# version_1_1.net
KiCad netlist of a schematic drawn in EAGLE
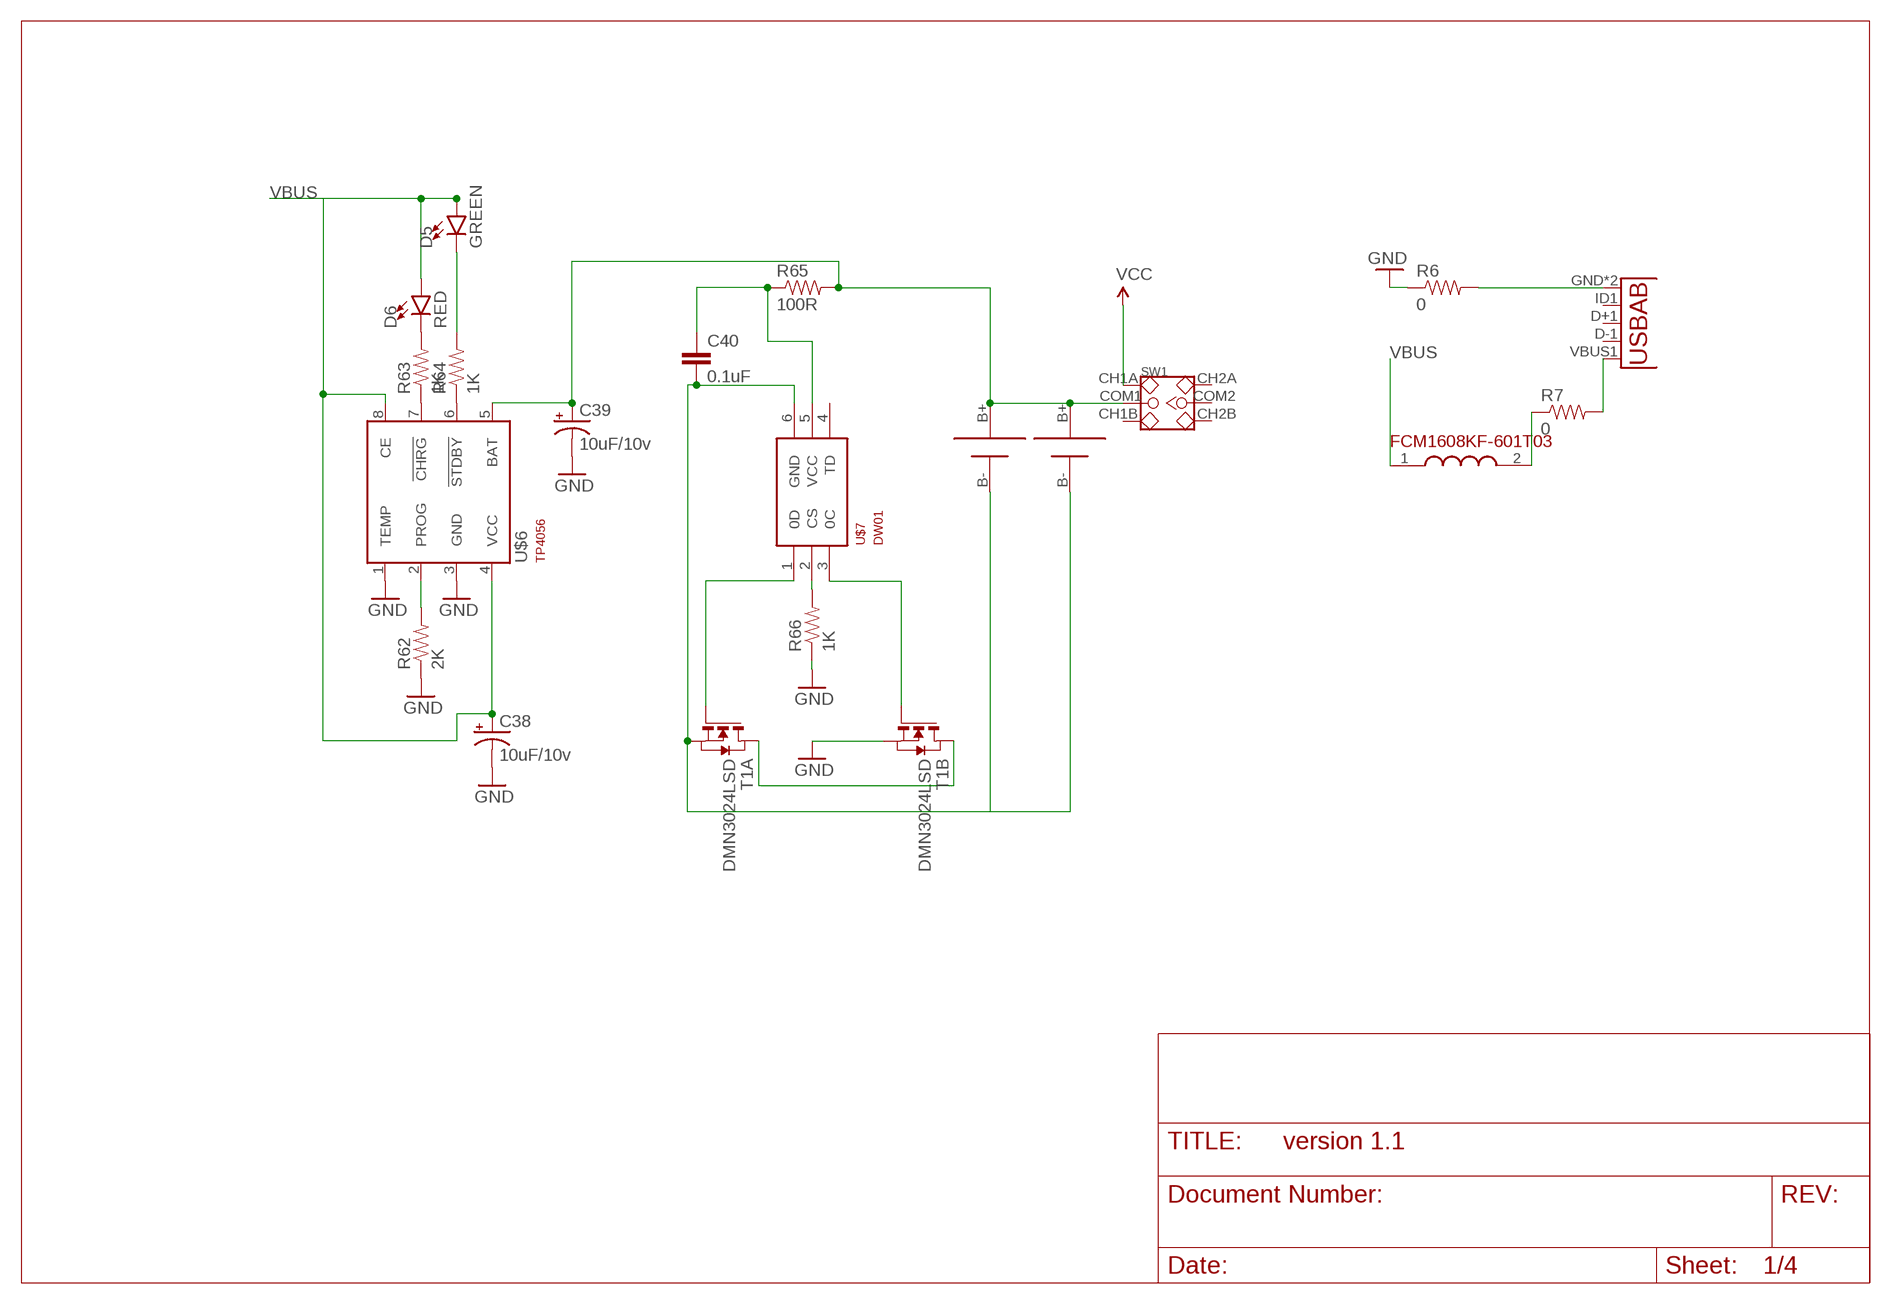
[diagram p0: schematic, sheet 1]
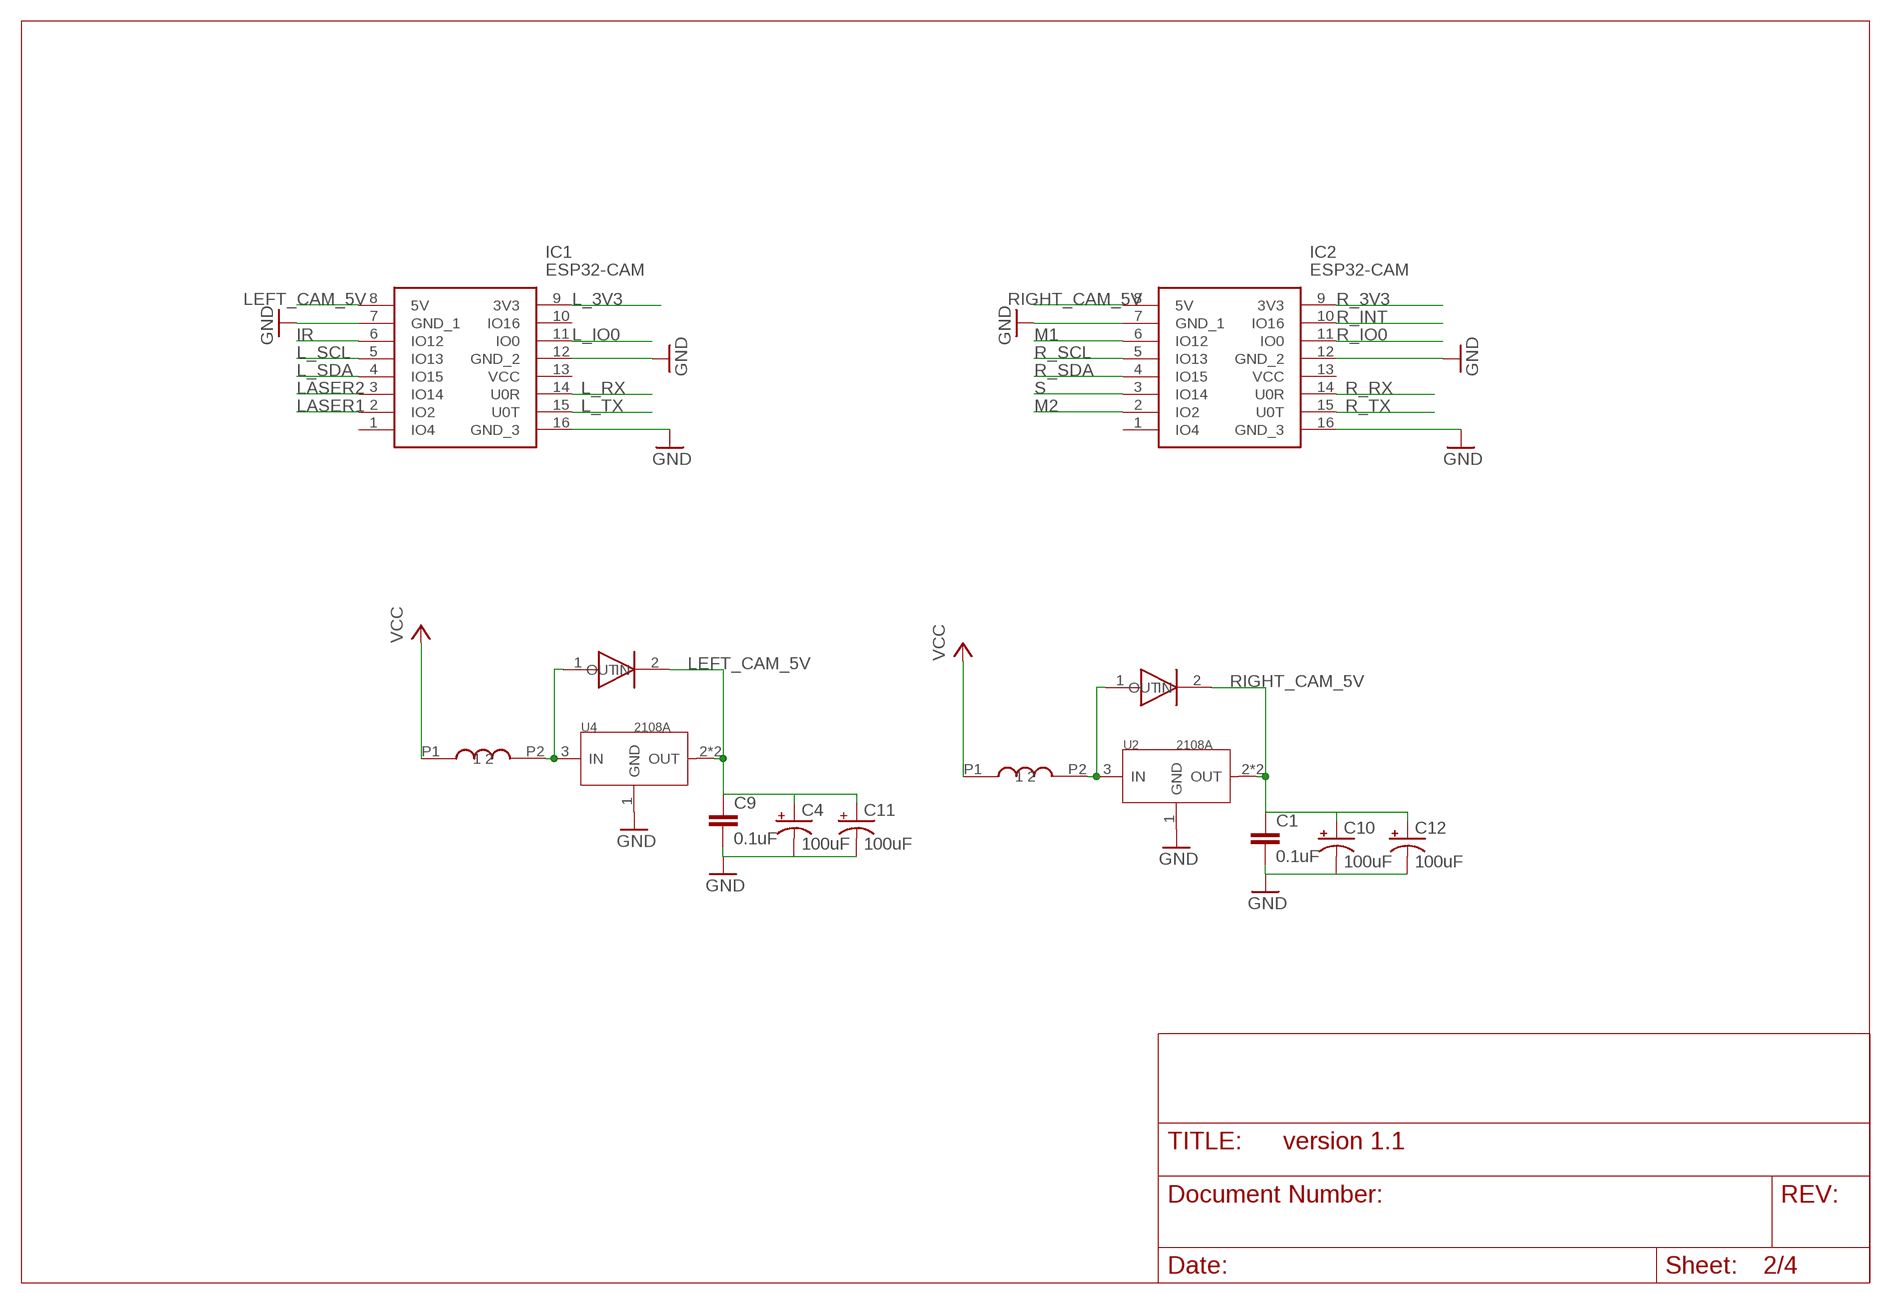
[diagram p1: schematic, sheet 2]
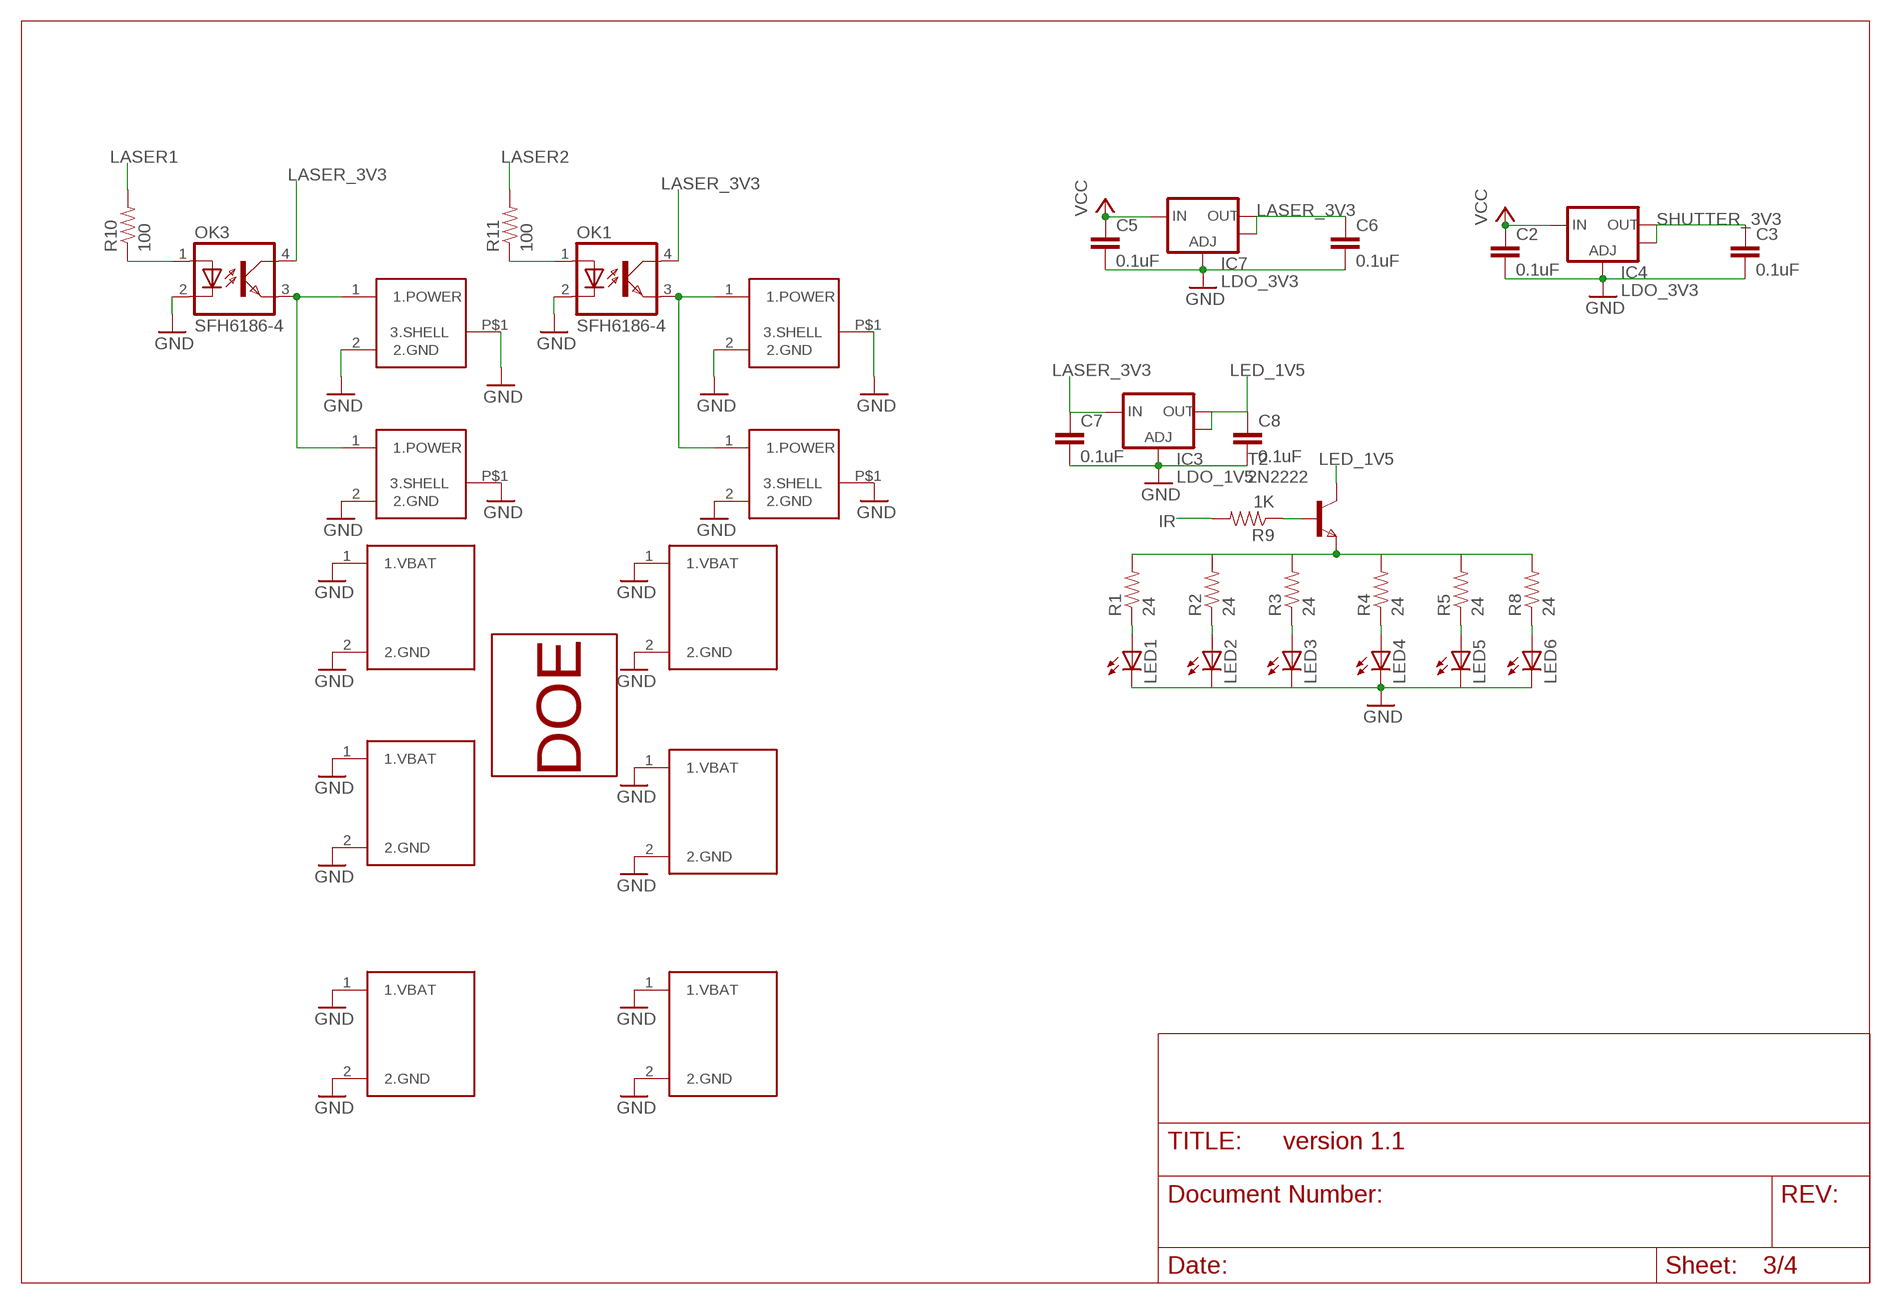
[diagram p2: schematic, sheet 3]
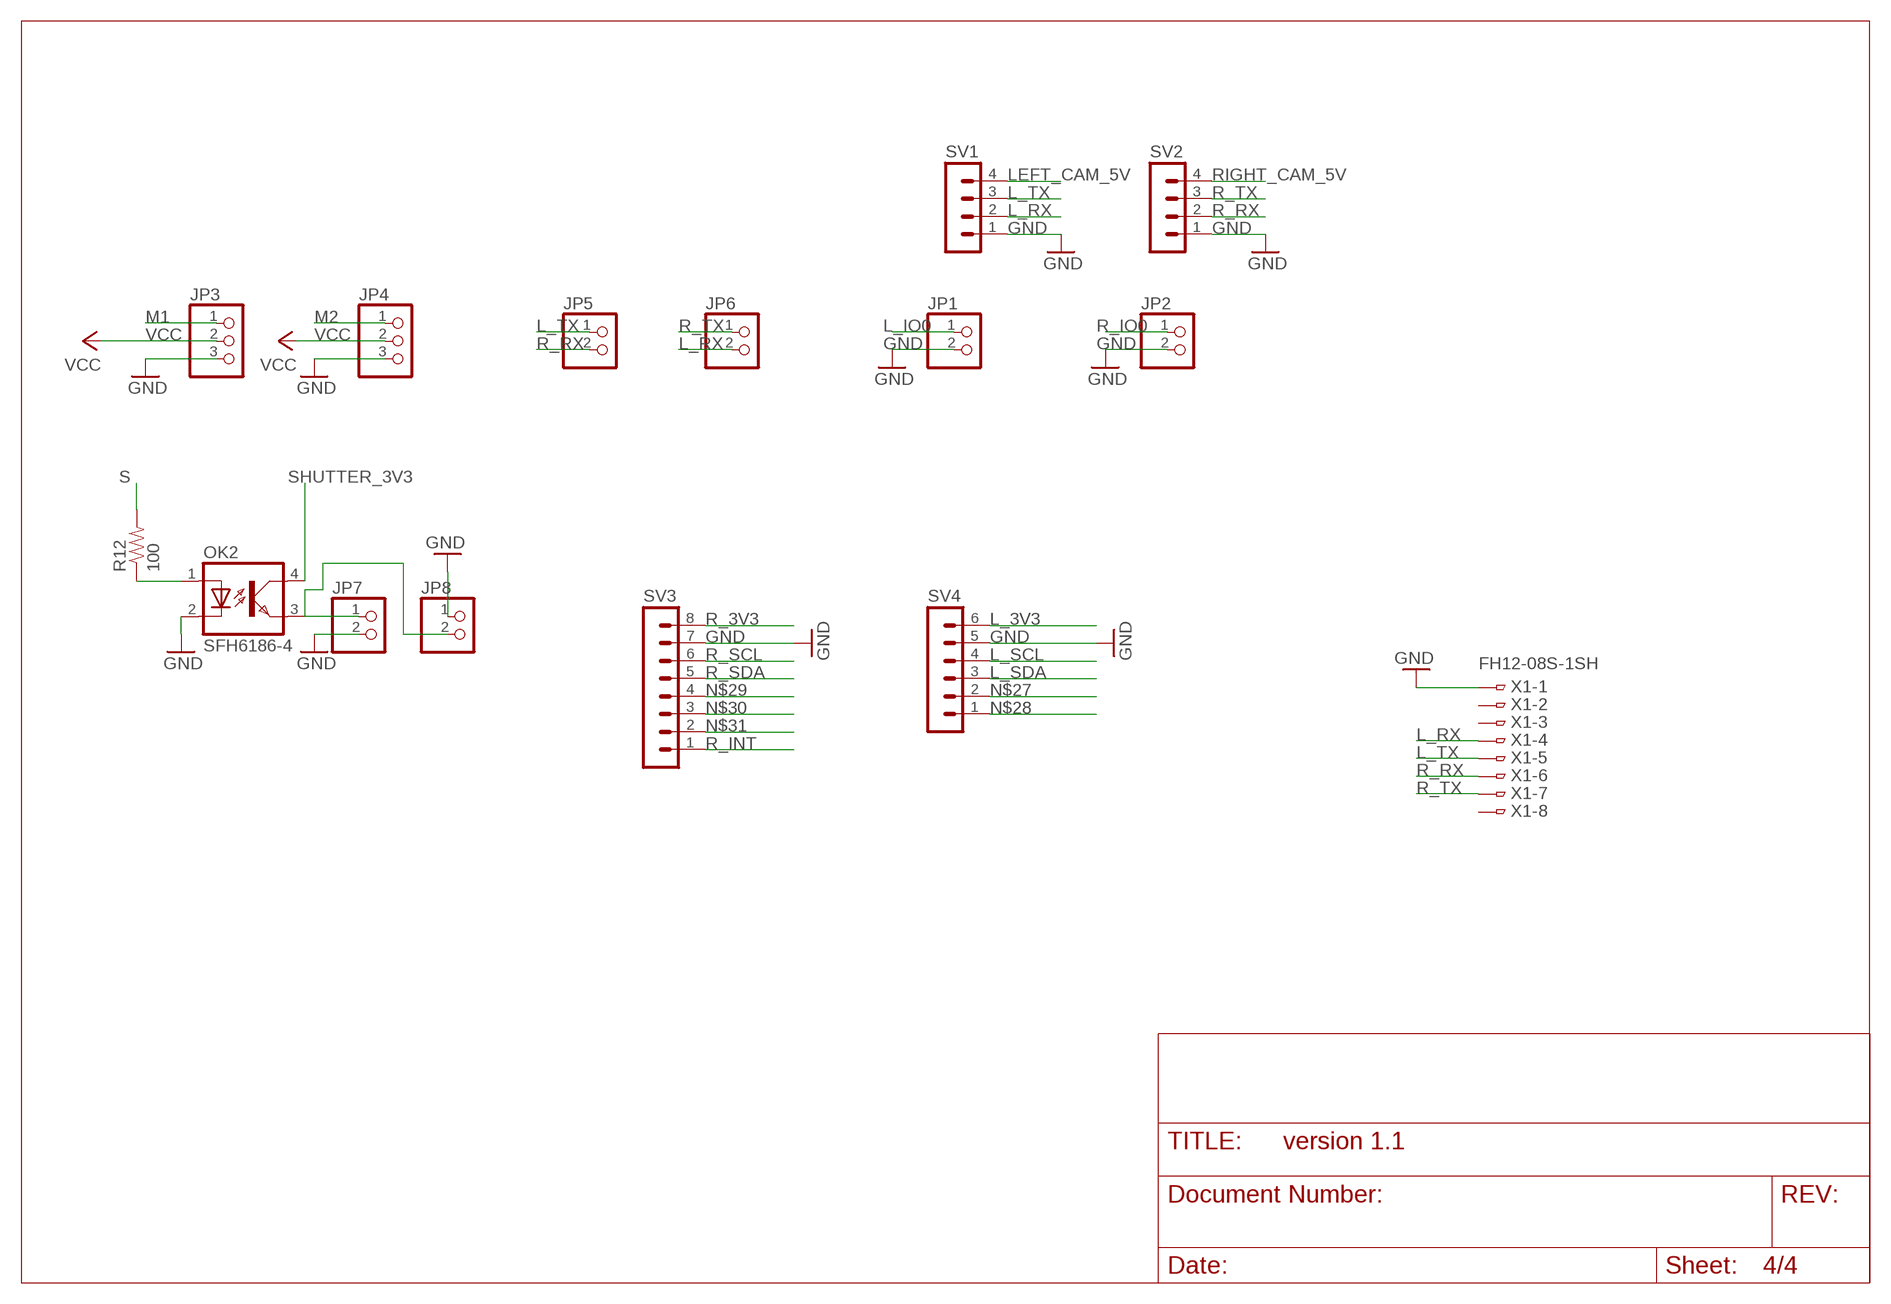
[diagram p3: schematic, sheet 4]

(export (version "E")
  (design (tool "Eeschema 10.0.6"))
  (components
    (comp (ref "C2")
      (value "0.1uF")
      (footprint "eagle-import:0603-CAP")
      (libsource (lib "eagle-import") (part "0.1UF-100V-10%(0603)"))
    )
    (comp (ref "C3")
      (value "0.1uF")
      (footprint "eagle-import:0603-CAP")
      (libsource (lib "eagle-import") (part "0.1UF-100V-10%(0603)"))
    )
    (comp (ref "C5")
      (value "0.1uF")
      (footprint "eagle-import:0603-CAP")
      (libsource (lib "eagle-import") (part "0.1UF-100V-10%(0603)"))
    )
    (comp (ref "C6")
      (value "0.1uF")
      (footprint "eagle-import:0603-CAP")
      (libsource (lib "eagle-import") (part "0.1UF-100V-10%(0603)"))
    )
    (comp (ref "C7")
      (value "0.1uF")
      (footprint "eagle-import:0603-CAP")
      (libsource (lib "eagle-import") (part "0.1UF-100V-10%(0603)"))
    )
    (comp (ref "C8")
      (value "0.1uF")
      (footprint "eagle-import:0603-CAP")
      (libsource (lib "eagle-import") (part "0.1UF-100V-10%(0603)"))
    )
    (comp (ref "IC3")
      (value "LDO_1V5")
      (footprint "eagle-import:SOT223")
      (libsource (lib "eagle-import") (part "V_REG_LM1117SOT223"))
    )
    (comp (ref "IC4")
      (value "LDO_3V3")
      (footprint "eagle-import:SOT223")
      (libsource (lib "eagle-import") (part "V_REG_LM1117SOT223"))
    )
    (comp (ref "IC7")
      (value "LDO_3V3")
      (footprint "eagle-import:SOT223")
      (libsource (lib "eagle-import") (part "V_REG_LM1117SOT223"))
    )
    (comp (ref "LED1")
      (value "LED5MM")
      (footprint "eagle-import:LED5MM")
      (libsource (lib "eagle-import") (part "LED5MM"))
    )
    (comp (ref "LED2")
      (value "LED5MM")
      (footprint "eagle-import:LED5MM")
      (libsource (lib "eagle-import") (part "LED5MM"))
    )
    (comp (ref "LED3")
      (value "LED5MM")
      (footprint "eagle-import:LED5MM")
      (libsource (lib "eagle-import") (part "LED5MM"))
    )
    (comp (ref "LED4")
      (value "LED5MM")
      (footprint "eagle-import:LED5MM")
      (libsource (lib "eagle-import") (part "LED5MM"))
    )
    (comp (ref "LED5")
      (value "LED5MM")
      (footprint "eagle-import:LED5MM")
      (libsource (lib "eagle-import") (part "LED5MM"))
    )
    (comp (ref "LED6")
      (value "LED5MM")
      (footprint "eagle-import:LED5MM")
      (libsource (lib "eagle-import") (part "LED5MM"))
    )
    (comp (ref "OK1")
      (value "SFH6186-4")
      (footprint "eagle-import:SMD4-7")
      (fields (field (name "MF") "VISHAY/TELEFUNKEN"))
      (libsource (lib "eagle-import") (part "SFH618?6-4"))
    )
    (comp (ref "OK3")
      (value "SFH6186-4")
      (footprint "eagle-import:SMD4-7")
      (fields (field (name "MF") "VISHAY/TELEFUNKEN"))
      (libsource (lib "eagle-import") (part "SFH618?6-4"))
    )
    (comp (ref "R1")
      (value "24")
      (footprint "eagle-import:0603-RES")
      (libsource (lib "eagle-import") (part "1KOHM1/10W1%(0603)"))
    )
    (comp (ref "R2")
      (value "24")
      (footprint "eagle-import:0603-RES")
      (libsource (lib "eagle-import") (part "1KOHM1/10W1%(0603)"))
    )
    (comp (ref "R3")
      (value "24")
      (footprint "eagle-import:0603-RES")
      (libsource (lib "eagle-import") (part "1KOHM1/10W1%(0603)"))
    )
    (comp (ref "R4")
      (value "24")
      (footprint "eagle-import:0603-RES")
      (libsource (lib "eagle-import") (part "1KOHM1/10W1%(0603)"))
    )
    (comp (ref "R5")
      (value "24")
      (footprint "eagle-import:0603-RES")
      (libsource (lib "eagle-import") (part "1KOHM1/10W1%(0603)"))
    )
    (comp (ref "R8")
      (value "24")
      (footprint "eagle-import:0603-RES")
      (libsource (lib "eagle-import") (part "1KOHM1/10W1%(0603)"))
    )
    (comp (ref "R9")
      (value "1K")
      (footprint "eagle-import:0603-RES")
      (libsource (lib "eagle-import") (part "1KOHM1/10W1%(0603)"))
    )
    (comp (ref "R10")
      (value "100")
      (footprint "eagle-import:0603-RES")
      (libsource (lib "eagle-import") (part "1KOHM1/10W1%(0603)"))
    )
    (comp (ref "R11")
      (value "100")
      (footprint "eagle-import:0603-RES")
      (libsource (lib "eagle-import") (part "1KOHM1/10W1%(0603)"))
    )
    (comp (ref "T2")
      (value "2N2222")
      (footprint "eagle-import:SOT-23")
      (libsource (lib "eagle-import") (part "FMMT451"))
    )
    (comp (ref "U$1")
      (value "OD-6.5MM-LASER")
      (footprint "eagle-import:OD-6.5MM-LASER")
      (libsource (lib "eagle-import") (part "OD-6.5MM-LASER"))
    )
    (comp (ref "U$2")
      (value "OD-6.5MM-LASER")
      (footprint "eagle-import:OD-6.5MM-LASER")
      (libsource (lib "eagle-import") (part "OD-6.5MM-LASER"))
    )
    (comp (ref "U$3")
      (value "DOE-MODULE")
      (footprint "eagle-import:DOE-MODULE")
      (libsource (lib "eagle-import") (part "DOE-MODULE"))
    )
    (comp (ref "U$9")
      (value "CR2025-HOLDER")
      (footprint "eagle-import:CR2025-HOLDER")
      (libsource (lib "eagle-import") (part "CR2025-HOLDER"))
    )
    (comp (ref "U$10")
      (value "CR2025-HOLDER")
      (footprint "eagle-import:CR2025-HOLDER")
      (libsource (lib "eagle-import") (part "CR2025-HOLDER"))
    )
    (comp (ref "U$11")
      (value "CR2025-HOLDER")
      (footprint "eagle-import:CR2025-HOLDER")
      (libsource (lib "eagle-import") (part "CR2025-HOLDER"))
    )
    (comp (ref "U$12")
      (value "CR2025-HOLDER")
      (footprint "eagle-import:CR2025-HOLDER")
      (libsource (lib "eagle-import") (part "CR2025-HOLDER"))
    )
    (comp (ref "U$17")
      (value "CR2025-HOLDER")
      (footprint "eagle-import:CR2025-HOLDER")
      (libsource (lib "eagle-import") (part "CR2025-HOLDER"))
    )
    (comp (ref "U$18")
      (value "CR2025-HOLDER")
      (footprint "eagle-import:CR2025-HOLDER")
      (libsource (lib "eagle-import") (part "CR2025-HOLDER"))
    )
    (comp (ref "U$19")
      (value "OD-9MM-LASER")
      (footprint "eagle-import:OD-9MM-LASER")
      (libsource (lib "eagle-import") (part "OD-9MM-LASER"))
    )
    (comp (ref "U$20")
      (value "OD-12MM-LASER")
      (footprint "eagle-import:OD-12MM-LASER")
      (libsource (lib "eagle-import") (part "OD-12MM-LASER"))
    )
    (comp (ref "C38")
      (value "10uF/10v")
      (footprint "eagle-import:EIA3216-KIT")
      (libsource (lib "eagle-import") (part "CAP_POL1206-KIT"))
    )
    (comp (ref "C39")
      (value "10uF/10v")
      (footprint "eagle-import:EIA3216-KIT")
      (libsource (lib "eagle-import") (part "CAP_POL1206-KIT"))
    )
    (comp (ref "C40")
      (value "0.1uF")
      (footprint "eagle-import:0603-CAP")
      (libsource (lib "eagle-import") (part "0.1UF-100V-10%(0603)"))
    )
    (comp (ref "D5")
      (value "GREEN")
      (footprint "eagle-import:LED-0603")
      (libsource (lib "eagle-import") (part "LED-BLUE0603"))
    )
    (comp (ref "D6")
      (value "RED")
      (footprint "eagle-import:LED-0603")
      (libsource (lib "eagle-import") (part "LED-BLUE0603"))
    )
    (comp (ref "R6")
      (value "0")
      (footprint "eagle-import:0805")
      (libsource (lib "eagle-import") (part "RESISTOR0805-RES"))
    )
    (comp (ref "R7")
      (value "0")
      (footprint "eagle-import:0805")
      (libsource (lib "eagle-import") (part "RESISTOR0805-RES"))
    )
    (comp (ref "R62")
      (value "2K")
      (footprint "eagle-import:0603-RES")
      (libsource (lib "eagle-import") (part "1KOHM1/10W1%(0603)"))
    )
    (comp (ref "R63")
      (value "1K")
      (footprint "eagle-import:0603-RES")
      (libsource (lib "eagle-import") (part "1KOHM1/10W1%(0603)"))
    )
    (comp (ref "R64")
      (value "1K")
      (footprint "eagle-import:0603-RES")
      (libsource (lib "eagle-import") (part "1KOHM1/10W1%(0603)"))
    )
    (comp (ref "R65")
      (value "100R")
      (footprint "eagle-import:0603-RES")
      (libsource (lib "eagle-import") (part "1KOHM1/10W1%(0603)"))
    )
    (comp (ref "R66")
      (value "1K")
      (footprint "eagle-import:0603-RES")
      (libsource (lib "eagle-import") (part "1KOHM1/10W1%(0603)"))
    )
    (comp (ref "SW1")
      (value "SMD-TOGGLE-SWITCH-2CH(2X3P-7X3.5MM)")
      (footprint "eagle-import:SW6-2.54-SMD-7.0X3.5X1.5MM")
      (libsource (lib "eagle-import") (part "SMD-TOGGLE-SWITCH-2CH(2X3P-7X3.5MM)"))
    )
    (comp (ref "T1")
      (value "DMN3024LSD")
      (footprint "eagle-import:TSSOP-8")
      (libsource (lib "eagle-import") (part "DMN3024LSD"))
    )
    (comp (ref "U$4")
      (value "FCM1608KF-601T03")
      (footprint "eagle-import:FCM1608KF-601T03")
      (libsource (lib "eagle-import") (part "FCM1608KF-601T03"))
    )
    (comp (ref "U$5")
      (value "18650SMD")
      (footprint "eagle-import:18650SMD")
      (libsource (lib "eagle-import") (part "18650SMD"))
    )
    (comp (ref "U$6")
      (value "TP4056")
      (footprint "eagle-import:SOT23-8")
      (libsource (lib "eagle-import") (part "TP4056"))
    )
    (comp (ref "U$7")
      (value "DW01")
      (footprint "eagle-import:SOT23-6")
      (libsource (lib "eagle-import") (part "DW01"))
    )
    (comp (ref "U$8")
      (value "18650SMD")
      (footprint "eagle-import:18650SMD")
      (libsource (lib "eagle-import") (part "18650SMD"))
    )
    (comp (ref "U1")
      (value "USB\"\"")
      (footprint "eagle-import:USB-MICRO-SMD")
      (libsource (lib "eagle-import") (part "USB{dblquote}{dblquote}"))
    )
    (comp (ref "JP1")
      (value "PINHD-1X2")
      (footprint "eagle-import:1X02")
      (libsource (lib "eagle-import") (part "PINHD-1X2"))
    )
    (comp (ref "JP2")
      (value "PINHD-1X2")
      (footprint "eagle-import:1X02")
      (libsource (lib "eagle-import") (part "PINHD-1X2"))
    )
    (comp (ref "JP3")
      (value "PINHD-1X3")
      (footprint "eagle-import:1X03")
      (libsource (lib "eagle-import") (part "PINHD-1X3"))
    )
    (comp (ref "JP4")
      (value "PINHD-1X3")
      (footprint "eagle-import:1X03")
      (libsource (lib "eagle-import") (part "PINHD-1X3"))
    )
    (comp (ref "JP5")
      (value "PINHD-1X2")
      (footprint "eagle-import:1X02")
      (libsource (lib "eagle-import") (part "PINHD-1X2"))
    )
    (comp (ref "JP6")
      (value "PINHD-1X2")
      (footprint "eagle-import:1X02")
      (libsource (lib "eagle-import") (part "PINHD-1X2"))
    )
    (comp (ref "JP7")
      (value "PINHD-1X2")
      (footprint "eagle-import:1X02")
      (libsource (lib "eagle-import") (part "PINHD-1X2"))
    )
    (comp (ref "JP8")
      (value "PINHD-1X2")
      (footprint "eagle-import:1X02")
      (libsource (lib "eagle-import") (part "PINHD-1X2"))
    )
    (comp (ref "OK2")
      (value "SFH6186-4")
      (footprint "eagle-import:SMD4-7")
      (fields (field (name "MF") "VISHAY/TELEFUNKEN"))
      (libsource (lib "eagle-import") (part "SFH618?6-4"))
    )
    (comp (ref "R12")
      (value "100")
      (footprint "eagle-import:0603-RES")
      (libsource (lib "eagle-import") (part "1KOHM1/10W1%(0603)"))
    )
    (comp (ref "SV1")
      (value "MA04-1")
      (footprint "eagle-import:MA04-1")
      (libsource (lib "eagle-import") (part "MA04-1"))
    )
    (comp (ref "SV2")
      (value "MA04-1")
      (footprint "eagle-import:MA04-1")
      (libsource (lib "eagle-import") (part "MA04-1"))
    )
    (comp (ref "SV3")
      (value "MA08-1")
      (footprint "eagle-import:MA08-1")
      (libsource (lib "eagle-import") (part "MA08-1"))
    )
    (comp (ref "SV4")
      (value "MA06-1")
      (footprint "eagle-import:MA06-1")
      (libsource (lib "eagle-import") (part "MA06-1"))
    )
    (comp (ref "X1")
      (value "FH12-08S-1SH")
      (footprint "eagle-import:FH12-08S-1SH")
      (libsource (lib "eagle-import") (part "FH12-08S-1SH"))
    )
    (comp (ref "C1")
      (value "0.1uF")
      (footprint "eagle-import:0603-CAP")
      (libsource (lib "eagle-import") (part "0.1UF-25V-5%(0603)"))
    )
    (comp (ref "C4")
      (value "100uF")
      (footprint "eagle-import:E_7260-38R")
      (libsource (lib "eagle-import") (part "CPOL-USE/7260-38R"))
    )
    (comp (ref "C9")
      (value "0.1uF")
      (footprint "eagle-import:0603-CAP")
      (libsource (lib "eagle-import") (part "0.1UF-25V-5%(0603)"))
    )
    (comp (ref "C10")
      (value "100uF")
      (footprint "eagle-import:E_7260-38R")
      (libsource (lib "eagle-import") (part "CPOL-USE/7260-38R"))
    )
    (comp (ref "C11")
      (value "100uF")
      (footprint "eagle-import:E_7260-38R")
      (libsource (lib "eagle-import") (part "CPOL-USE/7260-38R"))
    )
    (comp (ref "C12")
      (value "100uF")
      (footprint "eagle-import:E_7260-38R")
      (libsource (lib "eagle-import") (part "CPOL-USE/7260-38R"))
    )
    (comp (ref "IC1")
      (value "ESP32-CAM")
      (footprint "eagle-import:ESP32CAM")
      (libsource (lib "eagle-import") (part "ESP32-CAM"))
    )
    (comp (ref "IC2")
      (value "ESP32-CAM")
      (footprint "eagle-import:ESP32CAM")
      (libsource (lib "eagle-import") (part "ESP32-CAM"))
    )
    (comp (ref "U$13")
      (value "CD54")
      (footprint "eagle-import:CD54")
      (libsource (lib "eagle-import") (part "CD54"))
    )
    (comp (ref "U$14")
      (value "SMA-SS34")
      (footprint "eagle-import:SMA-SS34")
      (libsource (lib "eagle-import") (part "SMA-SS34"))
    )
    (comp (ref "U$15")
      (value "SMA-SS34")
      (footprint "eagle-import:SMA-SS34")
      (libsource (lib "eagle-import") (part "SMA-SS34"))
    )
    (comp (ref "U$16")
      (value "CD54")
      (footprint "eagle-import:CD54")
      (libsource (lib "eagle-import") (part "CD54"))
    )
    (comp (ref "U2")
      (value "2108A")
      (footprint "eagle-import:SOT-89")
      (fields (field (name "MPN") "CJA1117B-3.3"))
      (libsource (lib "eagle-import") (part "PMIC-CJA1117B-3.3(SOT-89)"))
    )
    (comp (ref "U4")
      (value "2108A")
      (footprint "eagle-import:SOT-89")
      (fields (field (name "MPN") "CJA1117B-3.3"))
      (libsource (lib "eagle-import") (part "PMIC-CJA1117B-3.3(SOT-89)"))
    )
  )
  (nets
    (net (code "1") (name "GND") (class "Default")
      (node (ref "C1") (pin "2") (pinfunction "2_2") (pintype "passive"))
      (node (ref "C10") (pin "-") (pinfunction "-_-") (pintype "passive"))
      (node (ref "C11") (pin "-") (pinfunction "-_-") (pintype "passive"))
      (node (ref "C12") (pin "-") (pinfunction "-_-") (pintype "passive"))
      (node (ref "C2") (pin "2") (pinfunction "2_2") (pintype "passive"))
      (node (ref "C3") (pin "2") (pinfunction "2_2") (pintype "passive"))
      (node (ref "C38") (pin "C") (pinfunction "-_C") (pintype "passive"))
      (node (ref "C39") (pin "C") (pinfunction "-_C") (pintype "passive"))
      (node (ref "C4") (pin "-") (pinfunction "-_-") (pintype "passive"))
      (node (ref "C5") (pin "2") (pinfunction "2_2") (pintype "passive"))
      (node (ref "C6") (pin "2") (pinfunction "2_2") (pintype "passive"))
      (node (ref "C7") (pin "2") (pinfunction "2_2") (pintype "passive"))
      (node (ref "C8") (pin "2") (pinfunction "2_2") (pintype "passive"))
      (node (ref "C9") (pin "2") (pinfunction "2_2") (pintype "passive"))
      (node (ref "IC1") (pin "12") (pinfunction "GND_2_12") (pintype "bidirectional"))
      (node (ref "IC1") (pin "16") (pinfunction "GND_3_16") (pintype "bidirectional"))
      (node (ref "IC1") (pin "7") (pinfunction "GND_1_7") (pintype "bidirectional"))
      (node (ref "IC2") (pin "12") (pinfunction "GND_2_12") (pintype "bidirectional"))
      (node (ref "IC2") (pin "16") (pinfunction "GND_3_16") (pintype "bidirectional"))
      (node (ref "IC2") (pin "7") (pinfunction "GND_1_7") (pintype "bidirectional"))
      (node (ref "IC3") (pin "1") (pinfunction "ADJ_1") (pintype "input"))
      (node (ref "IC4") (pin "1") (pinfunction "ADJ_1") (pintype "input"))
      (node (ref "IC7") (pin "1") (pinfunction "ADJ_1") (pintype "input"))
      (node (ref "JP1") (pin "2") (pinfunction "2_2") (pintype "passive"))
      (node (ref "JP2") (pin "2") (pinfunction "2_2") (pintype "passive"))
      (node (ref "JP3") (pin "3") (pinfunction "3_3") (pintype "passive"))
      (node (ref "JP4") (pin "3") (pinfunction "3_3") (pintype "passive"))
      (node (ref "JP7") (pin "2") (pinfunction "2_2") (pintype "passive"))
      (node (ref "JP8") (pin "1") (pinfunction "1_1") (pintype "passive"))
      (node (ref "LED1") (pin "K") (pinfunction "C_K") (pintype "passive"))
      (node (ref "LED2") (pin "K") (pinfunction "C_K") (pintype "passive"))
      (node (ref "LED3") (pin "K") (pinfunction "C_K") (pintype "passive"))
      (node (ref "LED4") (pin "K") (pinfunction "C_K") (pintype "passive"))
      (node (ref "LED5") (pin "K") (pinfunction "C_K") (pintype "passive"))
      (node (ref "LED6") (pin "K") (pinfunction "C_K") (pintype "passive"))
      (node (ref "OK1") (pin "2") (pinfunction "C_2") (pintype "passive"))
      (node (ref "OK2") (pin "2") (pinfunction "C_2") (pintype "passive"))
      (node (ref "OK3") (pin "2") (pinfunction "C_2") (pintype "passive"))
      (node (ref "R6") (pin "1") (pinfunction "1_1") (pintype "passive"))
      (node (ref "R62") (pin "1") (pinfunction "1_1") (pintype "passive"))
      (node (ref "R66") (pin "1") (pinfunction "1_1") (pintype "passive"))
      (node (ref "SV1") (pin "1") (pinfunction "1_1") (pintype "passive"))
      (node (ref "SV2") (pin "1") (pinfunction "1_1") (pintype "passive"))
      (node (ref "SV3") (pin "7") (pinfunction "7_7") (pintype "passive"))
      (node (ref "SV4") (pin "5") (pinfunction "5_5") (pintype "passive"))
      (node (ref "T1") (pin "6") (pinfunction "S_6") (pintype "passive"))
      (node (ref "T1") (pin "7") (pinfunction "S_7") (pintype "passive"))
      (node (ref "U$1") (pin "2") (pinfunction "2.GND_2") (pintype "bidirectional"))
      (node (ref "U$1") (pin "P$1") (pinfunction "3.SHELL_P$1") (pintype "bidirectional"))
      (node (ref "U$10") (pin "1") (pinfunction "1.VBAT_1") (pintype "bidirectional"))
      (node (ref "U$10") (pin "2") (pinfunction "2.GND_2") (pintype "bidirectional"))
      (node (ref "U$11") (pin "1") (pinfunction "1.VBAT_1") (pintype "bidirectional"))
      (node (ref "U$11") (pin "2") (pinfunction "2.GND_2") (pintype "bidirectional"))
      (node (ref "U$12") (pin "1") (pinfunction "1.VBAT_1") (pintype "bidirectional"))
      (node (ref "U$12") (pin "2") (pinfunction "2.GND_2") (pintype "bidirectional"))
      (node (ref "U$17") (pin "1") (pinfunction "1.VBAT_1") (pintype "bidirectional"))
      (node (ref "U$17") (pin "2") (pinfunction "2.GND_2") (pintype "bidirectional"))
      (node (ref "U$18") (pin "1") (pinfunction "1.VBAT_1") (pintype "bidirectional"))
      (node (ref "U$18") (pin "2") (pinfunction "2.GND_2") (pintype "bidirectional"))
      (node (ref "U$19") (pin "2") (pinfunction "2.GND_2") (pintype "bidirectional"))
      (node (ref "U$19") (pin "P$1") (pinfunction "3.SHELL_P$1") (pintype "bidirectional"))
      (node (ref "U$2") (pin "2") (pinfunction "2.GND_2") (pintype "bidirectional"))
      (node (ref "U$2") (pin "P$1") (pinfunction "3.SHELL_P$1") (pintype "bidirectional"))
      (node (ref "U$20") (pin "2") (pinfunction "2.GND_2") (pintype "bidirectional"))
      (node (ref "U$20") (pin "P$1") (pinfunction "3.SHELL_P$1") (pintype "bidirectional"))
      (node (ref "U$6") (pin "1") (pinfunction "TEMP_1") (pintype "bidirectional"))
      (node (ref "U$6") (pin "3") (pinfunction "GND_3") (pintype "bidirectional"))
      (node (ref "U$9") (pin "1") (pinfunction "1.VBAT_1") (pintype "bidirectional"))
      (node (ref "U$9") (pin "2") (pinfunction "2.GND_2") (pintype "bidirectional"))
      (node (ref "U2") (pin "1") (pinfunction "GND_1") (pintype "bidirectional"))
      (node (ref "U4") (pin "1") (pinfunction "GND_1") (pintype "bidirectional"))
      (node (ref "X1") (pin "1") (pinfunction "1_1") (pintype "passive"))
    )
    (net (code "2") (name "IR") (class "Default")
      (node (ref "IC1") (pin "6") (pinfunction "IO12_6") (pintype "bidirectional"))
      (node (ref "R9") (pin "2") (pinfunction "2_2") (pintype "passive"))
    )
    (net (code "3") (name "LASER1") (class "Default")
      (node (ref "IC1") (pin "2") (pinfunction "IO2_2") (pintype "bidirectional"))
      (node (ref "R10") (pin "2") (pinfunction "2_2") (pintype "passive"))
    )
    (net (code "4") (name "LASER2") (class "Default")
      (node (ref "IC1") (pin "3") (pinfunction "IO14_3") (pintype "bidirectional"))
      (node (ref "R11") (pin "2") (pinfunction "2_2") (pintype "passive"))
    )
    (net (code "5") (name "LASER_3V3") (class "Default")
      (node (ref "C6") (pin "1") (pinfunction "1_1") (pintype "passive"))
      (node (ref "C7") (pin "1") (pinfunction "1_1") (pintype "passive"))
      (node (ref "IC3") (pin "3") (pinfunction "IN_3") (pintype "input"))
      (node (ref "IC7") (pin "2") (pinfunction "OUT_2") (pintype "output"))
      (node (ref "IC7") (pin "4") (pinfunction "OUT_4") (pintype "output"))
      (node (ref "OK1") (pin "4") (pinfunction "COL_4") (pintype "passive"))
      (node (ref "OK3") (pin "4") (pinfunction "COL_4") (pintype "passive"))
    )
    (net (code "6") (name "LED_1V5") (class "Default")
      (node (ref "C8") (pin "1") (pinfunction "1_1") (pintype "passive"))
      (node (ref "IC3") (pin "2") (pinfunction "OUT_2") (pintype "output"))
      (node (ref "IC3") (pin "4") (pinfunction "OUT_4") (pintype "output"))
      (node (ref "T2") (pin "1") (pinfunction "C_1") (pintype "passive"))
    )
    (net (code "7") (name "LEFT_CAM_5V") (class "Default")
      (node (ref "C11") (pin "+") (pinfunction "+_+") (pintype "passive"))
      (node (ref "C4") (pin "+") (pinfunction "+_+") (pintype "passive"))
      (node (ref "C9") (pin "1") (pinfunction "1_1") (pintype "passive"))
      (node (ref "IC1") (pin "8") (pinfunction "5V_8") (pintype "bidirectional"))
      (node (ref "SV1") (pin "4") (pinfunction "4_4") (pintype "passive"))
      (node (ref "U$14") (pin "2") (pinfunction "OUT_2") (pintype "bidirectional"))
      (node (ref "U4") (pin "2") (pinfunction "OUT_2") (pintype "bidirectional"))
      (node (ref "U4") (pin "4") (pinfunction "OUT_4") (pintype "bidirectional"))
    )
    (net (code "8") (name "L_3V3") (class "Default")
      (node (ref "IC1") (pin "9") (pinfunction "3V3_9") (pintype "bidirectional"))
      (node (ref "SV4") (pin "6") (pinfunction "6_6") (pintype "passive"))
    )
    (net (code "9") (name "L_IO0") (class "Default")
      (node (ref "IC1") (pin "11") (pinfunction "IO0_11") (pintype "bidirectional"))
      (node (ref "JP1") (pin "1") (pinfunction "1_1") (pintype "passive"))
    )
    (net (code "10") (name "L_RX") (class "Default")
      (node (ref "IC1") (pin "14") (pinfunction "U0R_14") (pintype "bidirectional"))
      (node (ref "JP6") (pin "2") (pinfunction "2_2") (pintype "passive"))
      (node (ref "SV1") (pin "2") (pinfunction "2_2") (pintype "passive"))
      (node (ref "X1") (pin "4") (pinfunction "1_4") (pintype "passive"))
    )
    (net (code "11") (name "L_SCL") (class "Default")
      (node (ref "IC1") (pin "5") (pinfunction "IO13_5") (pintype "bidirectional"))
      (node (ref "SV4") (pin "4") (pinfunction "4_4") (pintype "passive"))
    )
    (net (code "12") (name "L_SDA") (class "Default")
      (node (ref "IC1") (pin "4") (pinfunction "IO15_4") (pintype "bidirectional"))
      (node (ref "SV4") (pin "3") (pinfunction "3_3") (pintype "passive"))
    )
    (net (code "13") (name "L_TX") (class "Default")
      (node (ref "IC1") (pin "15") (pinfunction "U0T_15") (pintype "bidirectional"))
      (node (ref "JP5") (pin "1") (pinfunction "1_1") (pintype "passive"))
      (node (ref "SV1") (pin "3") (pinfunction "3_3") (pintype "passive"))
      (node (ref "X1") (pin "5") (pinfunction "1_5") (pintype "passive"))
    )
    (net (code "14") (name "M1") (class "Default")
      (node (ref "IC2") (pin "6") (pinfunction "IO12_6") (pintype "bidirectional"))
      (node (ref "JP3") (pin "1") (pinfunction "1_1") (pintype "passive"))
    )
    (net (code "15") (name "M2") (class "Default")
      (node (ref "IC2") (pin "2") (pinfunction "IO2_2") (pintype "bidirectional"))
      (node (ref "JP4") (pin "1") (pinfunction "1_1") (pintype "passive"))
    )
    (net (code "16") (name "N$27") (class "Default")
      (node (ref "SV4") (pin "2") (pinfunction "2_2") (pintype "passive"))
    )
    (net (code "17") (name "N$28") (class "Default")
      (node (ref "SV4") (pin "1") (pinfunction "1_1") (pintype "passive"))
    )
    (net (code "18") (name "N$29") (class "Default")
      (node (ref "SV3") (pin "4") (pinfunction "4_4") (pintype "passive"))
    )
    (net (code "19") (name "N$30") (class "Default")
      (node (ref "SV3") (pin "3") (pinfunction "3_3") (pintype "passive"))
    )
    (net (code "20") (name "N$31") (class "Default")
      (node (ref "SV3") (pin "2") (pinfunction "2_2") (pintype "passive"))
    )
    (net (code "21") (name "Net-(C39-+)") (class "Default")
      (node (ref "C39") (pin "A") (pinfunction "+_A") (pintype "passive"))
      (node (ref "R65") (pin "2") (pinfunction "2_2") (pintype "passive"))
      (node (ref "SW1") (pin "COM1") (pinfunction "COM1_COM1") (pintype "bidirectional"))
      (node (ref "U$5") (pin "B+") (pinfunction "B+_B+") (pintype "bidirectional"))
      (node (ref "U$6") (pin "5") (pinfunction "BAT_5") (pintype "bidirectional"))
      (node (ref "U$8") (pin "B+") (pinfunction "B+_B+") (pintype "bidirectional"))
    )
    (net (code "22") (name "Net-(D5-PadC)") (class "Default")
      (node (ref "D5") (pin "C") (pinfunction "C_C") (pintype "passive"))
      (node (ref "R64") (pin "2") (pinfunction "2_2") (pintype "passive"))
    )
    (net (code "23") (name "Net-(D6-PadC)") (class "Default")
      (node (ref "D6") (pin "C") (pinfunction "C_C") (pintype "passive"))
      (node (ref "R63") (pin "2") (pinfunction "2_2") (pintype "passive"))
    )
    (net (code "24") (name "Net-(LED1-PadA)") (class "Default")
      (node (ref "LED1") (pin "A") (pinfunction "A_A") (pintype "passive"))
      (node (ref "R1") (pin "1") (pinfunction "1_1") (pintype "passive"))
    )
    (net (code "25") (name "Net-(LED2-PadA)") (class "Default")
      (node (ref "LED2") (pin "A") (pinfunction "A_A") (pintype "passive"))
      (node (ref "R2") (pin "1") (pinfunction "1_1") (pintype "passive"))
    )
    (net (code "26") (name "Net-(LED3-PadA)") (class "Default")
      (node (ref "LED3") (pin "A") (pinfunction "A_A") (pintype "passive"))
      (node (ref "R3") (pin "1") (pinfunction "1_1") (pintype "passive"))
    )
    (net (code "27") (name "Net-(LED4-PadA)") (class "Default")
      (node (ref "LED4") (pin "A") (pinfunction "A_A") (pintype "passive"))
      (node (ref "R4") (pin "1") (pinfunction "1_1") (pintype "passive"))
    )
    (net (code "28") (name "Net-(LED5-PadA)") (class "Default")
      (node (ref "LED5") (pin "A") (pinfunction "A_A") (pintype "passive"))
      (node (ref "R5") (pin "1") (pinfunction "1_1") (pintype "passive"))
    )
    (net (code "29") (name "Net-(LED6-PadA)") (class "Default")
      (node (ref "LED6") (pin "A") (pinfunction "A_A") (pintype "passive"))
      (node (ref "R8") (pin "1") (pinfunction "1_1") (pintype "passive"))
    )
    (net (code "30") (name "Net-(OK1-A)") (class "Default")
      (node (ref "OK1") (pin "1") (pinfunction "A_1") (pintype "passive"))
      (node (ref "R11") (pin "1") (pinfunction "1_1") (pintype "passive"))
    )
    (net (code "31") (name "Net-(OK1-EMIT)") (class "Default")
      (node (ref "OK1") (pin "3") (pinfunction "EMIT_3") (pintype "passive"))
      (node (ref "U$19") (pin "1") (pinfunction "1.POWER_1") (pintype "bidirectional"))
      (node (ref "U$2") (pin "1") (pinfunction "1.POWER_1") (pintype "bidirectional"))
    )
    (net (code "32") (name "Net-(OK2-A)") (class "Default")
      (node (ref "OK2") (pin "1") (pinfunction "A_1") (pintype "passive"))
      (node (ref "R12") (pin "1") (pinfunction "1_1") (pintype "passive"))
    )
    (net (code "33") (name "Net-(OK2-EMIT)") (class "Default")
      (node (ref "JP7") (pin "1") (pinfunction "1_1") (pintype "passive"))
      (node (ref "JP8") (pin "2") (pinfunction "2_2") (pintype "passive"))
      (node (ref "OK2") (pin "3") (pinfunction "EMIT_3") (pintype "passive"))
    )
    (net (code "34") (name "Net-(OK3-A)") (class "Default")
      (node (ref "OK3") (pin "1") (pinfunction "A_1") (pintype "passive"))
      (node (ref "R10") (pin "1") (pinfunction "1_1") (pintype "passive"))
    )
    (net (code "35") (name "Net-(OK3-EMIT)") (class "Default")
      (node (ref "OK3") (pin "3") (pinfunction "EMIT_3") (pintype "passive"))
      (node (ref "U$1") (pin "1") (pinfunction "1.POWER_1") (pintype "bidirectional"))
      (node (ref "U$20") (pin "1") (pinfunction "1.POWER_1") (pintype "bidirectional"))
    )
    (net (code "36") (name "Net-(R6-Pad2)") (class "Default")
      (node (ref "R6") (pin "2") (pinfunction "2_2") (pintype "passive"))
      (node (ref "U1") (pin "GND") (pinfunction "GND_GND") (pintype "bidirectional"))
      (node (ref "U1") (pin "GND1") (pinfunction "GND_GND1") (pintype "bidirectional"))
    )
    (net (code "37") (name "Net-(T1A-D)") (class "Default")
      (node (ref "T1") (pin "1") (pinfunction "D_1") (pintype "passive"))
      (node (ref "T1") (pin "8") (pinfunction "D_8") (pintype "passive"))
    )
    (net (code "38") (name "Net-(T1A-G)") (class "Default")
      (node (ref "T1") (pin "4") (pinfunction "G_4") (pintype "passive"))
      (node (ref "U$7") (pin "1") (pinfunction "0D_1") (pintype "bidirectional"))
    )
    (net (code "39") (name "Net-(T1B-G)") (class "Default")
      (node (ref "T1") (pin "5") (pinfunction "G_5") (pintype "passive"))
      (node (ref "U$7") (pin "3") (pinfunction "0C_3") (pintype "bidirectional"))
    )
    (net (code "40") (name "Net-(T2-B)") (class "Default")
      (node (ref "R9") (pin "1") (pinfunction "1_1") (pintype "passive"))
      (node (ref "T2") (pin "3") (pinfunction "B_3") (pintype "passive"))
    )
    (net (code "41") (name "Net-(T2-E)") (class "Default")
      (node (ref "R1") (pin "2") (pinfunction "2_2") (pintype "passive"))
      (node (ref "R2") (pin "2") (pinfunction "2_2") (pintype "passive"))
      (node (ref "R3") (pin "2") (pinfunction "2_2") (pintype "passive"))
      (node (ref "R4") (pin "2") (pinfunction "2_2") (pintype "passive"))
      (node (ref "R5") (pin "2") (pinfunction "2_2") (pintype "passive"))
      (node (ref "R8") (pin "2") (pinfunction "2_2") (pintype "passive"))
      (node (ref "T2") (pin "2") (pinfunction "E_2") (pintype "passive"))
    )
    (net (code "42") (name "Net-(U$4-2.OUT)") (class "Default")
      (node (ref "R7") (pin "1") (pinfunction "1_1") (pintype "passive"))
      (node (ref "U$4") (pin "2") (pinfunction "2.OUT_2") (pintype "bidirectional"))
    )
    (net (code "43") (name "Net-(U$6-PROG)") (class "Default")
      (node (ref "R62") (pin "2") (pinfunction "2_2") (pintype "passive"))
      (node (ref "U$6") (pin "2") (pinfunction "PROG_2") (pintype "bidirectional"))
    )
    (net (code "44") (name "Net-(U$6-~{CHRG})") (class "Default")
      (node (ref "R63") (pin "1") (pinfunction "1_1") (pintype "passive"))
      (node (ref "U$6") (pin "7") (pinfunction "~{CHRG}_7") (pintype "bidirectional"))
    )
    (net (code "45") (name "Net-(U$6-~{STDBY})") (class "Default")
      (node (ref "R64") (pin "1") (pinfunction "1_1") (pintype "passive"))
      (node (ref "U$6") (pin "6") (pinfunction "~{STDBY}_6") (pintype "bidirectional"))
    )
    (net (code "46") (name "Net-(U$7-CS)") (class "Default")
      (node (ref "R66") (pin "2") (pinfunction "2_2") (pintype "passive"))
      (node (ref "U$7") (pin "2") (pinfunction "CS_2") (pintype "bidirectional"))
    )
    (net (code "47") (name "Net-(U$7-GND)") (class "Default")
      (node (ref "C40") (pin "2") (pinfunction "2_2") (pintype "passive"))
      (node (ref "T1") (pin "2") (pinfunction "S_2") (pintype "passive"))
      (node (ref "T1") (pin "3") (pinfunction "S_3") (pintype "passive"))
      (node (ref "U$5") (pin "B-") (pinfunction "B-_B-") (pintype "bidirectional"))
      (node (ref "U$7") (pin "6") (pinfunction "GND_6") (pintype "bidirectional"))
      (node (ref "U$8") (pin "B-") (pinfunction "B-_B-") (pintype "bidirectional"))
    )
    (net (code "48") (name "Net-(U$7-VCC)") (class "Default")
      (node (ref "C40") (pin "1") (pinfunction "1_1") (pintype "passive"))
      (node (ref "R65") (pin "1") (pinfunction "1_1") (pintype "passive"))
      (node (ref "U$7") (pin "5") (pinfunction "VCC_5") (pintype "bidirectional"))
    )
    (net (code "49") (name "Net-(U$13-2)") (class "Default")
      (node (ref "U$13") (pin "P2") (pinfunction "2_P2") (pintype "bidirectional"))
      (node (ref "U$14") (pin "1") (pinfunction "IN_1") (pintype "input"))
      (node (ref "U4") (pin "3") (pinfunction "IN_3") (pintype "bidirectional"))
    )
    (net (code "50") (name "Net-(U$15-IN)") (class "Default")
      (node (ref "U$15") (pin "1") (pinfunction "IN_1") (pintype "input"))
      (node (ref "U$16") (pin "P2") (pinfunction "2_P2") (pintype "bidirectional"))
      (node (ref "U2") (pin "3") (pinfunction "IN_3") (pintype "bidirectional"))
    )
    (net (code "51") (name "Net-(U1-VBUS)") (class "Default")
      (node (ref "R7") (pin "2") (pinfunction "2_2") (pintype "passive"))
      (node (ref "U1") (pin "VBUS1") (pinfunction "VBUS_VBUS1") (pintype "bidirectional"))
    )
    (net (code "52") (name "RIGHT_CAM_5V") (class "Default")
      (node (ref "C1") (pin "1") (pinfunction "1_1") (pintype "passive"))
      (node (ref "C10") (pin "+") (pinfunction "+_+") (pintype "passive"))
      (node (ref "C12") (pin "+") (pinfunction "+_+") (pintype "passive"))
      (node (ref "IC2") (pin "8") (pinfunction "5V_8") (pintype "bidirectional"))
      (node (ref "SV2") (pin "4") (pinfunction "4_4") (pintype "passive"))
      (node (ref "U$15") (pin "2") (pinfunction "OUT_2") (pintype "bidirectional"))
      (node (ref "U2") (pin "2") (pinfunction "OUT_2") (pintype "bidirectional"))
      (node (ref "U2") (pin "4") (pinfunction "OUT_4") (pintype "bidirectional"))
    )
    (net (code "53") (name "R_3V3") (class "Default")
      (node (ref "IC2") (pin "9") (pinfunction "3V3_9") (pintype "bidirectional"))
      (node (ref "SV3") (pin "8") (pinfunction "8_8") (pintype "passive"))
    )
    (net (code "54") (name "R_INT") (class "Default")
      (node (ref "IC2") (pin "10") (pinfunction "IO16_10") (pintype "bidirectional"))
      (node (ref "SV3") (pin "1") (pinfunction "1_1") (pintype "passive"))
    )
    (net (code "55") (name "R_IO0") (class "Default")
      (node (ref "IC2") (pin "11") (pinfunction "IO0_11") (pintype "bidirectional"))
      (node (ref "JP2") (pin "1") (pinfunction "1_1") (pintype "passive"))
    )
    (net (code "56") (name "R_RX") (class "Default")
      (node (ref "IC2") (pin "14") (pinfunction "U0R_14") (pintype "bidirectional"))
      (node (ref "JP5") (pin "2") (pinfunction "2_2") (pintype "passive"))
      (node (ref "SV2") (pin "2") (pinfunction "2_2") (pintype "passive"))
      (node (ref "X1") (pin "6") (pinfunction "1_6") (pintype "passive"))
    )
    (net (code "57") (name "R_SCL") (class "Default")
      (node (ref "IC2") (pin "5") (pinfunction "IO13_5") (pintype "bidirectional"))
      (node (ref "SV3") (pin "6") (pinfunction "6_6") (pintype "passive"))
    )
    (net (code "58") (name "R_SDA") (class "Default")
      (node (ref "IC2") (pin "4") (pinfunction "IO15_4") (pintype "bidirectional"))
      (node (ref "SV3") (pin "5") (pinfunction "5_5") (pintype "passive"))
    )
    (net (code "59") (name "R_TX") (class "Default")
      (node (ref "IC2") (pin "15") (pinfunction "U0T_15") (pintype "bidirectional"))
      (node (ref "JP6") (pin "1") (pinfunction "1_1") (pintype "passive"))
      (node (ref "SV2") (pin "3") (pinfunction "3_3") (pintype "passive"))
      (node (ref "X1") (pin "7") (pinfunction "1_7") (pintype "passive"))
    )
    (net (code "60") (name "S") (class "Default")
      (node (ref "IC2") (pin "3") (pinfunction "IO14_3") (pintype "bidirectional"))
      (node (ref "R12") (pin "2") (pinfunction "2_2") (pintype "passive"))
    )
    (net (code "61") (name "SHUTTER_3V3") (class "Default")
      (node (ref "C3") (pin "1") (pinfunction "1_1") (pintype "passive"))
      (node (ref "IC4") (pin "2") (pinfunction "OUT_2") (pintype "output"))
      (node (ref "IC4") (pin "4") (pinfunction "OUT_4") (pintype "output"))
      (node (ref "OK2") (pin "4") (pinfunction "COL_4") (pintype "passive"))
    )
    (net (code "62") (name "VBUS") (class "Default")
      (node (ref "C38") (pin "A") (pinfunction "+_A") (pintype "passive"))
      (node (ref "D5") (pin "A") (pinfunction "A_A") (pintype "passive"))
      (node (ref "D6") (pin "A") (pinfunction "A_A") (pintype "passive"))
      (node (ref "U$4") (pin "1") (pinfunction "1.IN_1") (pintype "bidirectional"))
      (node (ref "U$6") (pin "4") (pinfunction "VCC_4") (pintype "bidirectional"))
      (node (ref "U$6") (pin "8") (pinfunction "CE_8") (pintype "bidirectional"))
    )
    (net (code "63") (name "VCC") (class "Default")
      (node (ref "C2") (pin "1") (pinfunction "1_1") (pintype "passive"))
      (node (ref "C5") (pin "1") (pinfunction "1_1") (pintype "passive"))
      (node (ref "IC4") (pin "3") (pinfunction "IN_3") (pintype "input"))
      (node (ref "IC7") (pin "3") (pinfunction "IN_3") (pintype "input"))
      (node (ref "JP3") (pin "2") (pinfunction "2_2") (pintype "passive"))
      (node (ref "JP4") (pin "2") (pinfunction "2_2") (pintype "passive"))
      (node (ref "SW1") (pin "CH1A") (pinfunction "CH1A_CH1A") (pintype "bidirectional"))
      (node (ref "U$13") (pin "P1") (pinfunction "1_P1") (pintype "bidirectional"))
      (node (ref "U$16") (pin "P1") (pinfunction "1_P1") (pintype "bidirectional"))
    )
    (net (code "64") (name "unconnected-(IC1-IO4-Pad1)") (class "Default")
      (node (ref "IC1") (pin "1") (pinfunction "IO4_1") (pintype "bidirectional"))
    )
    (net (code "65") (name "unconnected-(IC1-IO16-Pad10)") (class "Default")
      (node (ref "IC1") (pin "10") (pinfunction "IO16_10") (pintype "bidirectional"))
    )
    (net (code "66") (name "unconnected-(IC1-VCC-Pad13)") (class "Default")
      (node (ref "IC1") (pin "13") (pinfunction "VCC_13") (pintype "bidirectional"))
    )
    (net (code "67") (name "unconnected-(IC2-IO4-Pad1)") (class "Default")
      (node (ref "IC2") (pin "1") (pinfunction "IO4_1") (pintype "bidirectional"))
    )
    (net (code "68") (name "unconnected-(IC2-VCC-Pad13)") (class "Default")
      (node (ref "IC2") (pin "13") (pinfunction "VCC_13") (pintype "bidirectional"))
    )
    (net (code "69") (name "unconnected-(SW1-PadCH1B)") (class "Default")
      (node (ref "SW1") (pin "CH1B") (pinfunction "CH1B_CH1B") (pintype "bidirectional"))
    )
    (net (code "70") (name "unconnected-(SW1-PadCH2A)") (class "Default")
      (node (ref "SW1") (pin "CH2A") (pinfunction "CH2A_CH2A") (pintype "bidirectional"))
    )
    (net (code "71") (name "unconnected-(SW1-PadCH2B)") (class "Default")
      (node (ref "SW1") (pin "CH2B") (pinfunction "CH2B_CH2B") (pintype "bidirectional"))
    )
    (net (code "72") (name "unconnected-(SW1-PadCOM2)") (class "Default")
      (node (ref "SW1") (pin "COM2") (pinfunction "COM2_COM2") (pintype "bidirectional"))
    )
    (net (code "73") (name "unconnected-(U$7-TD-Pad4)") (class "Default")
      (node (ref "U$7") (pin "4") (pinfunction "TD_4") (pintype "bidirectional"))
    )
    (net (code "74") (name "unconnected-(U1-D+-PadD+1)") (class "Default")
      (node (ref "U1") (pin "D+1") (pinfunction "D+_D+1") (pintype "bidirectional"))
    )
    (net (code "75") (name "unconnected-(U1-D--PadD-1)") (class "Default")
      (node (ref "U1") (pin "D-1") (pinfunction "D-_D-1") (pintype "bidirectional"))
    )
    (net (code "76") (name "unconnected-(U1-USBID-PadID1)") (class "Default")
      (node (ref "U1") (pin "ID1") (pinfunction "USBID_ID1") (pintype "bidirectional"))
    )
    (net (code "77") (name "unconnected-(X1B-1-Pad2)") (class "Default")
      (node (ref "X1") (pin "2") (pinfunction "1_2") (pintype "passive"))
    )
    (net (code "78") (name "unconnected-(X1C-1-Pad3)") (class "Default")
      (node (ref "X1") (pin "3") (pinfunction "1_3") (pintype "passive"))
    )
    (net (code "79") (name "unconnected-(X1H-1-Pad8)") (class "Default")
      (node (ref "X1") (pin "8") (pinfunction "1_8") (pintype "passive"))
    )
  )
)
